# trinketm0fader_60mm.net
KiCad netlist of a schematic drawn in EAGLE
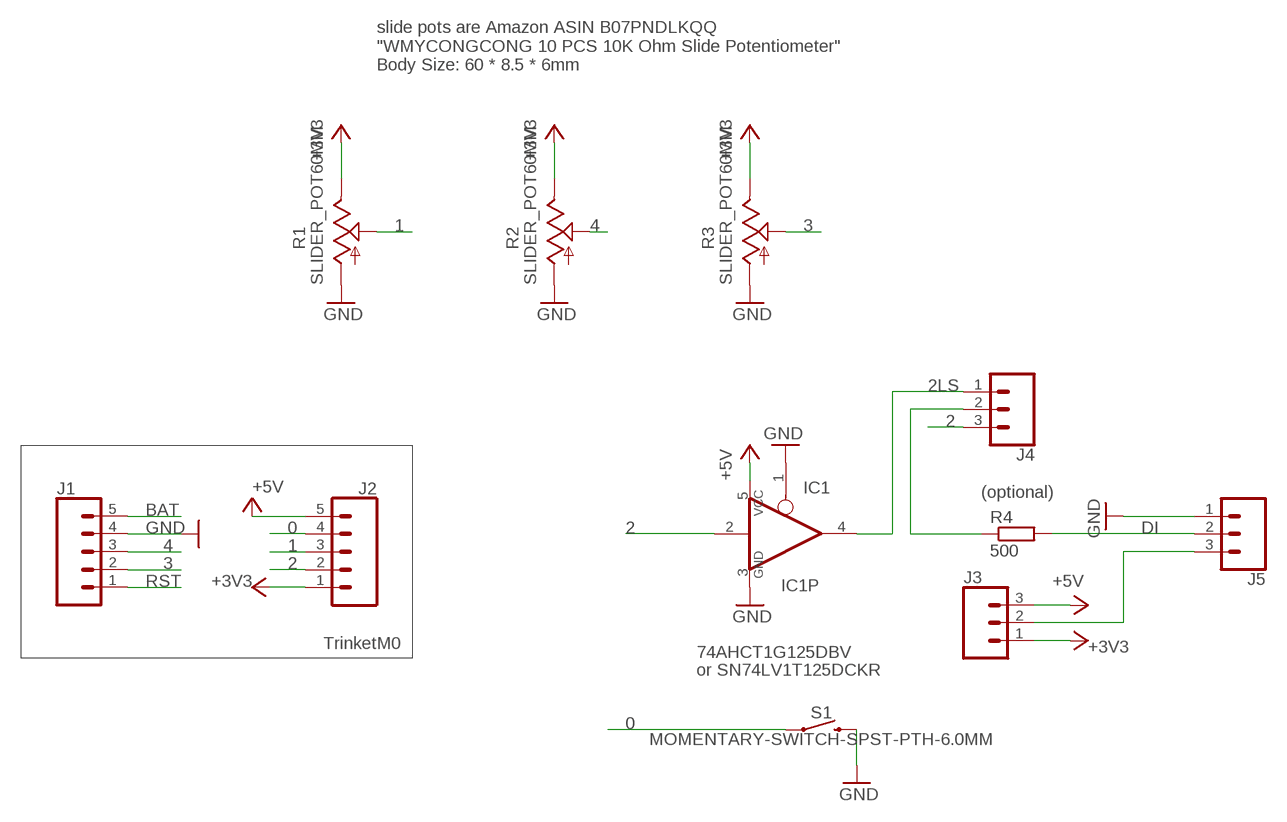
[diagram p0: schematic, sheet 1]

(export (version "E")
  (design (tool "Eeschema 10.0.6"))
  (components
    (comp (ref "IC1")
      (value "74AHCT1G125DBV")
      (footprint "eagle-import:SOT23-5")
      (libsource (lib "eagle-import") (part "741G125DBVAHCT"))
    )
    (comp (ref "J1")
      (value "CONN_05")
      (footprint "eagle-import:1X05")
      (libsource (lib "eagle-import") (part "CONN_05"))
    )
    (comp (ref "J2")
      (value "CONN_05")
      (footprint "eagle-import:1X05")
      (libsource (lib "eagle-import") (part "CONN_05"))
    )
    (comp (ref "J3")
      (value "CONN_03")
      (footprint "eagle-import:1X03")
      (libsource (lib "eagle-import") (part "CONN_03"))
    )
    (comp (ref "J4")
      (value "CONN_03")
      (footprint "eagle-import:1X03")
      (libsource (lib "eagle-import") (part "CONN_03"))
    )
    (comp (ref "J5")
      (value "CONN_03")
      (footprint "eagle-import:1X03")
      (libsource (lib "eagle-import") (part "CONN_03"))
    )
    (comp (ref "R1")
      (value "SLIDER_POT60MM")
      (footprint "eagle-import:SLIDEPOT_60MM")
      (libsource (lib "eagle-import") (part "SLIDER_POT60MM"))
    )
    (comp (ref "R2")
      (value "SLIDER_POT60MM")
      (footprint "eagle-import:SLIDEPOT_60MM")
      (libsource (lib "eagle-import") (part "SLIDER_POT60MM"))
    )
    (comp (ref "R3")
      (value "SLIDER_POT60MM")
      (footprint "eagle-import:SLIDEPOT_60MM")
      (libsource (lib "eagle-import") (part "SLIDER_POT60MM"))
    )
    (comp (ref "R4")
      (value "500")
      (footprint "eagle-import:R0603")
      (libsource (lib "eagle-import") (part "R-EU_R0603"))
    )
    (comp (ref "S1")
      (value "MOMENTARY-SWITCH-SPST-PTH-6.0MM")
      (footprint "eagle-import:TACTILE_SWITCH_PTH_6.0MM")
      (libsource (lib "eagle-import") (part "MOMENTARY-SWITCH-SPST-PTH-6.0MM"))
    )
  )
  (nets
    (net (code "1") (name "+3V3") (class "Default")
      (node (ref "J2") (pin "1") (pinfunction "1_1") (pintype "passive"))
      (node (ref "J3") (pin "1") (pinfunction "1_1") (pintype "passive"))
      (node (ref "R1") (pin "V") (pinfunction "V_V") (pintype "passive"))
      (node (ref "R2") (pin "V") (pinfunction "V_V") (pintype "passive"))
      (node (ref "R3") (pin "V") (pinfunction "V_V") (pintype "passive"))
    )
    (net (code "2") (name "+5V") (class "Default")
      (node (ref "IC1") (pin "5") (pinfunction "VCC_5") (pintype "power_in"))
      (node (ref "J2") (pin "5") (pinfunction "5_5") (pintype "passive"))
      (node (ref "J3") (pin "3") (pinfunction "3_3") (pintype "passive"))
    )
    (net (code "3") (name "/0") (class "Default")
      (node (ref "J2") (pin "4") (pinfunction "4_4") (pintype "passive"))
      (node (ref "S1") (pin "1") (pinfunction "1_1") (pintype "passive"))
    )
    (net (code "4") (name "/1") (class "Default")
      (node (ref "J2") (pin "3") (pinfunction "3_3") (pintype "passive"))
      (node (ref "R1") (pin "W") (pinfunction "W_W") (pintype "passive"))
    )
    (net (code "5") (name "/2") (class "Default")
      (node (ref "IC1") (pin "2") (pinfunction "I_2") (pintype "input"))
      (node (ref "J2") (pin "2") (pinfunction "2_2") (pintype "passive"))
      (node (ref "J4") (pin "3") (pinfunction "3_3") (pintype "passive"))
    )
    (net (code "6") (name "/2LS") (class "Default")
      (node (ref "IC1") (pin "4") (pinfunction "O_4") (pintype "tri_state"))
      (node (ref "J4") (pin "1") (pinfunction "1_1") (pintype "passive"))
    )
    (net (code "7") (name "/3") (class "Default")
      (node (ref "J1") (pin "2") (pinfunction "2_2") (pintype "passive"))
      (node (ref "R3") (pin "W") (pinfunction "W_W") (pintype "passive"))
    )
    (net (code "8") (name "/4") (class "Default")
      (node (ref "J1") (pin "3") (pinfunction "3_3") (pintype "passive"))
      (node (ref "R2") (pin "W") (pinfunction "W_W") (pintype "passive"))
    )
    (net (code "9") (name "/BAT") (class "Default")
      (node (ref "J1") (pin "5") (pinfunction "5_5") (pintype "passive"))
    )
    (net (code "10") (name "/DI") (class "Default")
      (node (ref "J5") (pin "2") (pinfunction "2_2") (pintype "passive"))
      (node (ref "R4") (pin "2") (pinfunction "2_2") (pintype "passive"))
    )
    (net (code "11") (name "/RST") (class "Default")
      (node (ref "J1") (pin "1") (pinfunction "1_1") (pintype "passive"))
    )
    (net (code "12") (name "GND") (class "Default")
      (node (ref "IC1") (pin "1") (pinfunction "OE_1") (pintype "input"))
      (node (ref "IC1") (pin "3") (pinfunction "GND_3") (pintype "power_in"))
      (node (ref "J1") (pin "4") (pinfunction "4_4") (pintype "passive"))
      (node (ref "J5") (pin "1") (pinfunction "1_1") (pintype "passive"))
      (node (ref "R1") (pin "G") (pinfunction "G_G") (pintype "passive"))
      (node (ref "R2") (pin "G") (pinfunction "G_G") (pintype "passive"))
      (node (ref "R3") (pin "G") (pinfunction "G_G") (pintype "passive"))
      (node (ref "S1") (pin "3") (pinfunction "2_3") (pintype "passive"))
    )
    (net (code "13") (name "Net-(J3-Pad2)") (class "Default")
      (node (ref "J3") (pin "2") (pinfunction "2_2") (pintype "passive"))
      (node (ref "J5") (pin "3") (pinfunction "3_3") (pintype "passive"))
    )
    (net (code "14") (name "Net-(J4-Pad2)") (class "Default")
      (node (ref "J4") (pin "2") (pinfunction "2_2") (pintype "passive"))
      (node (ref "R4") (pin "1") (pinfunction "1_1") (pintype "passive"))
    )
  )
)
